# ProDoc_promicro_e22P_Tomas_2026-05-28.net
KiCad netlist of a schematic drawn in EasyEDA Pro
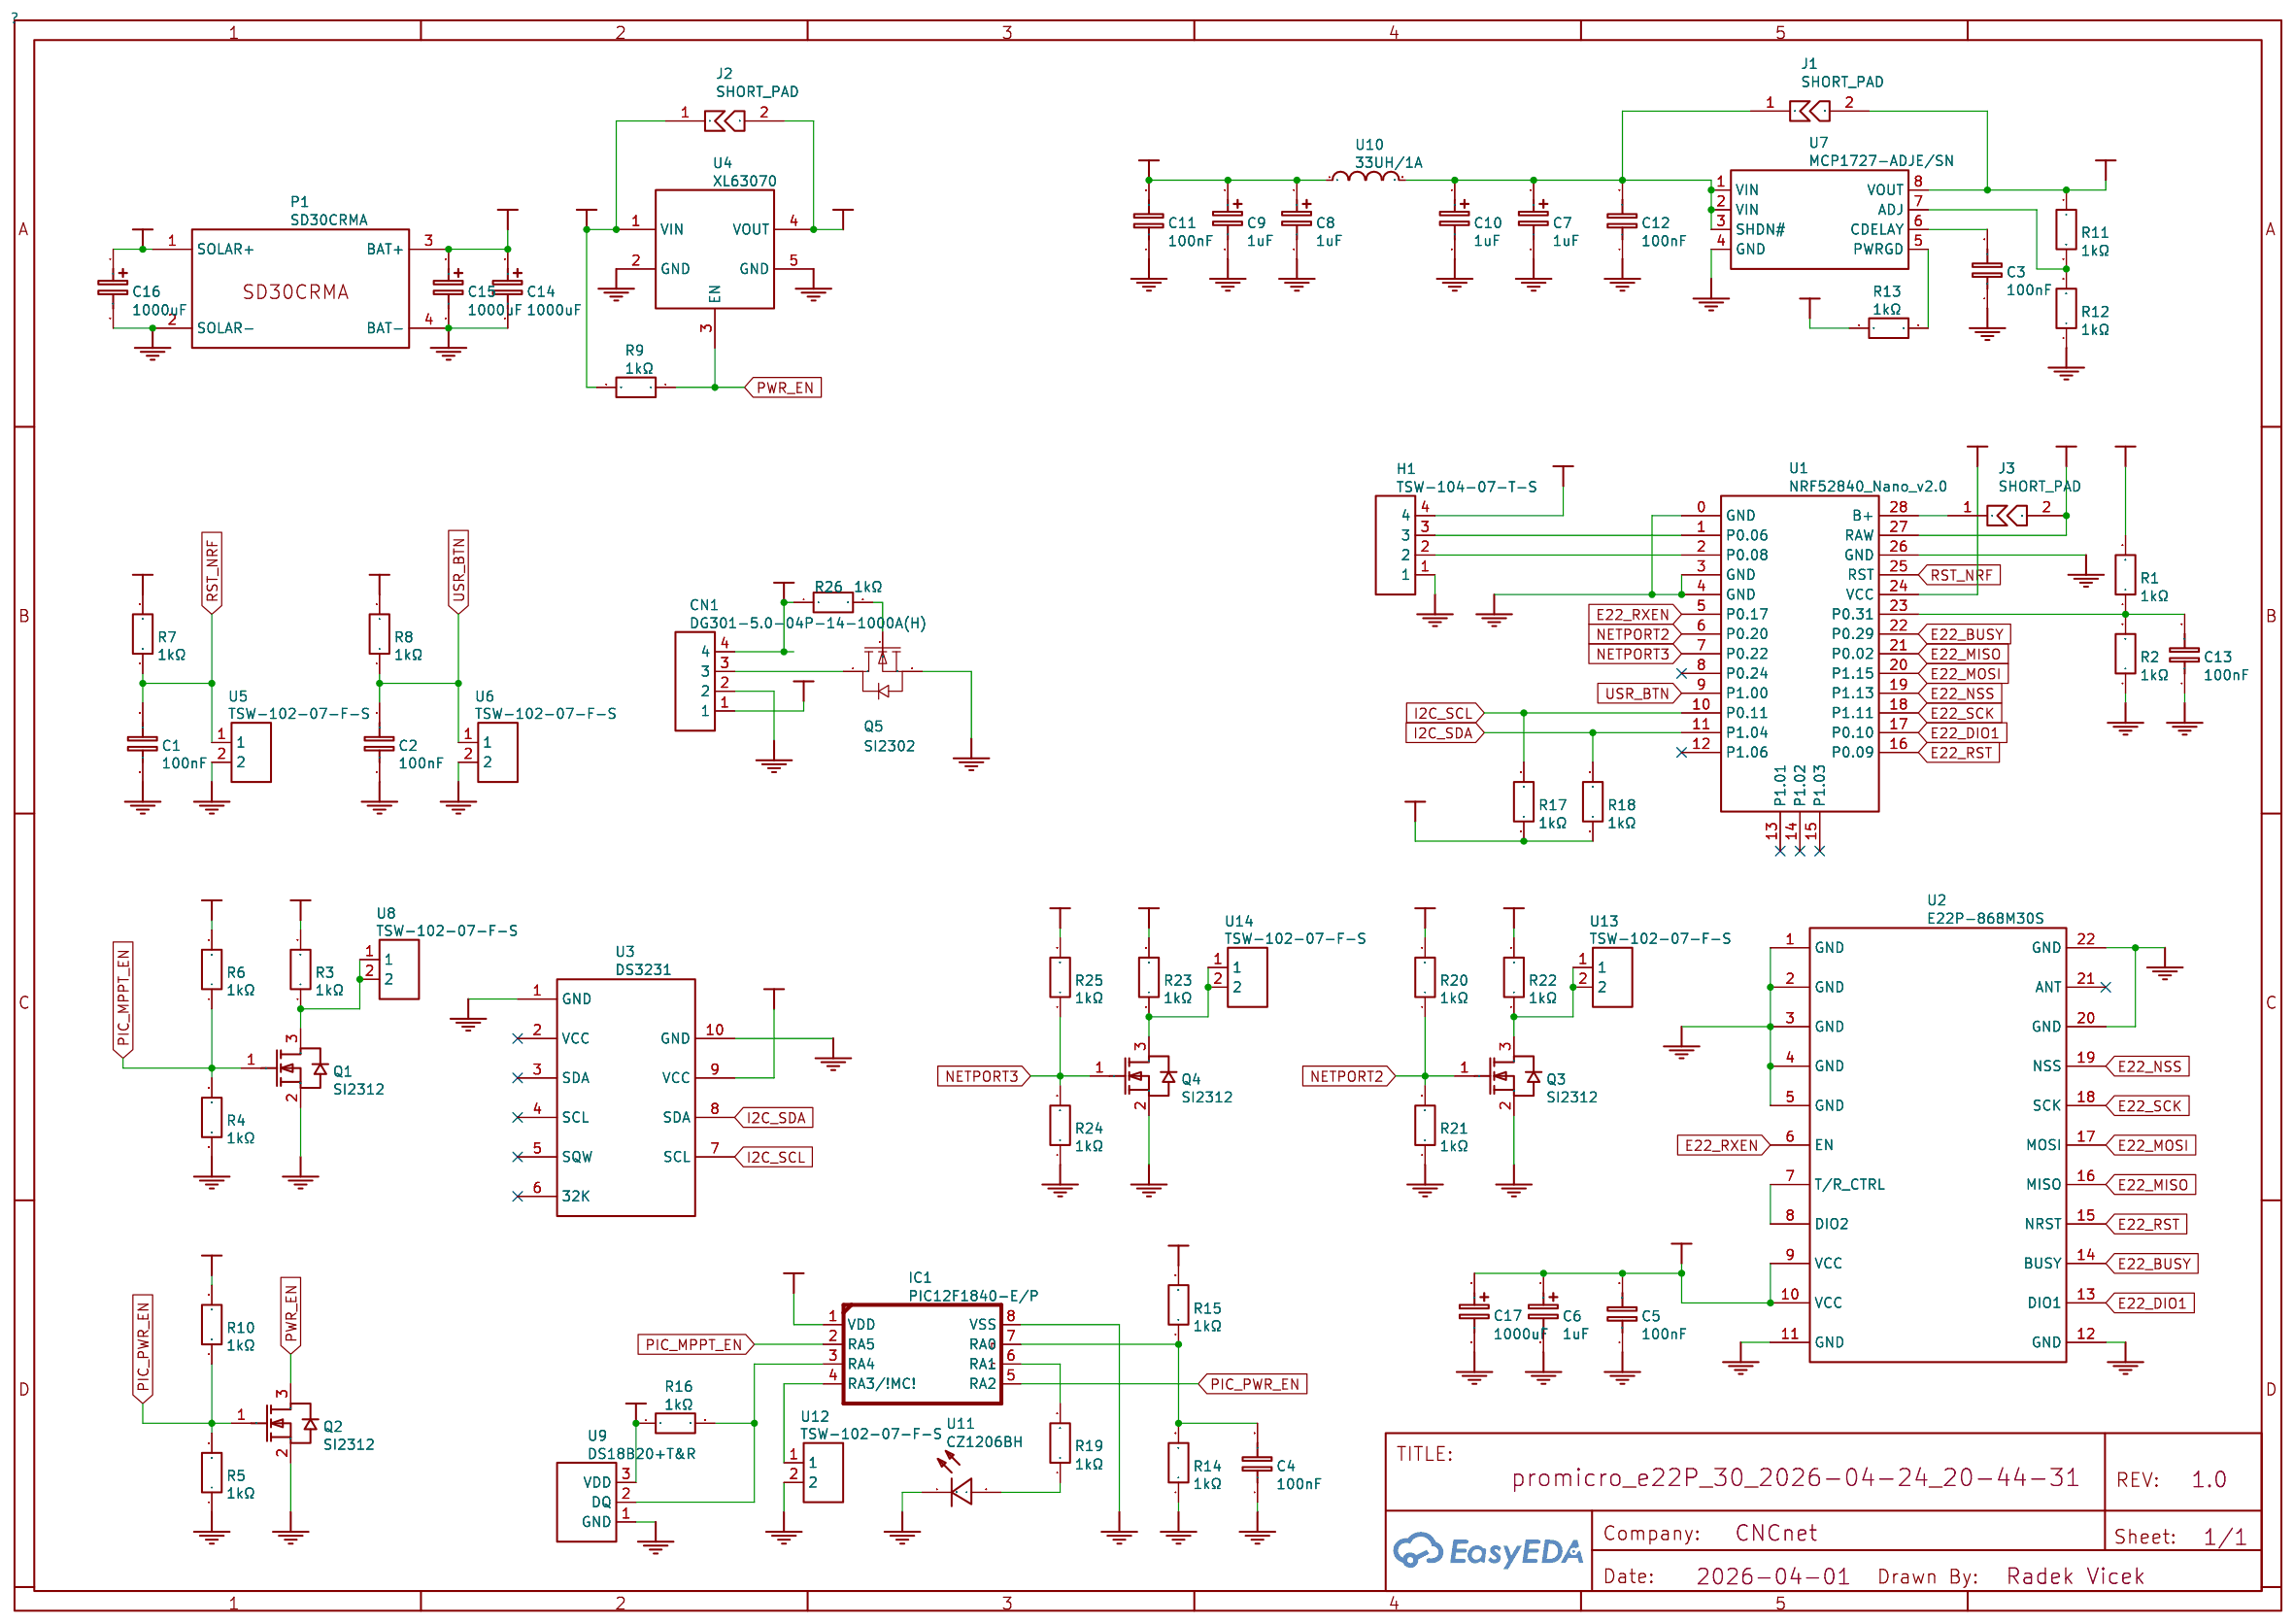
[diagram p0: schematic sheet]

(export (version "E")
  (design (tool "Eeschema 10.0.6"))
  (components
    (comp (ref "C1")
      (value "100nF")
      (description "Capacitance:100nF Tolerance:±10% Tolerance:±10% Voltage Rating:50V Temperature Coefficient:-")
      (fields
        (field (name "Manufacturer Part") "CT41G-0805-2X1-50V-0.1uF-K(N)")
        (field (name "Manufacturer") "TORCH(火炬)")
      )
      (libsource (lib "easyedapro") (part "0.1u"))
    )
    (comp (ref "C2")
      (value "100nF")
      (description "Capacitance:100nF Tolerance:±10% Tolerance:±10% Voltage Rating:50V Temperature Coefficient:-")
      (fields
        (field (name "Manufacturer Part") "CT41G-0805-2X1-50V-0.1uF-K(N)")
        (field (name "Manufacturer") "TORCH(火炬)")
      )
      (libsource (lib "easyedapro") (part "0.1u"))
    )
    (comp (ref "C3")
      (value "100nF")
      (description "Capacitance:100nF Tolerance:±10% Tolerance:±10% Voltage Rating:50V Temperature Coefficient:-")
      (fields
        (field (name "Manufacturer Part") "CT41G-0805-2X1-50V-0.1uF-K(N)")
        (field (name "Manufacturer") "TORCH(火炬)")
      )
      (libsource (lib "easyedapro") (part "0.1u"))
    )
    (comp (ref "C4")
      (value "100nF")
      (description "Capacitance:100nF Tolerance:±10% Tolerance:±10% Voltage Rating:50V Temperature Coefficient:-")
      (fields
        (field (name "Manufacturer Part") "CT41G-0805-2X1-50V-0.1uF-K(N)")
        (field (name "Manufacturer") "TORCH(火炬)")
      )
      (libsource (lib "easyedapro") (part "0.1u"))
    )
    (comp (ref "C5")
      (value "100nF")
      (description "Capacitance:100nF Tolerance:±10% Tolerance:±10% Voltage Rating:50V Temperature Coefficient:-")
      (fields
        (field (name "Manufacturer Part") "CT41G-0805-2X1-50V-0.1uF-K(N)")
        (field (name "Manufacturer") "TORCH(火炬)")
      )
      (libsource (lib "easyedapro") (part "0.1u"))
    )
    (comp (ref "C6")
      (value "1uF")
      (fields (field (name "Manufacturer Part") "TAJB105K035RNJ") (field (name "Manufacturer") "Kyocera AVX"))
      (libsource (lib "easyedapro") (part "1u"))
    )
    (comp (ref "C7")
      (value "1uF")
      (fields (field (name "Manufacturer Part") "TAJB105K035RNJ") (field (name "Manufacturer") "Kyocera AVX"))
      (libsource (lib "easyedapro") (part "1u"))
    )
    (comp (ref "C8")
      (value "1uF")
      (fields (field (name "Manufacturer Part") "TAJB105K035RNJ") (field (name "Manufacturer") "Kyocera AVX"))
      (libsource (lib "easyedapro") (part "1u"))
    )
    (comp (ref "C9")
      (value "1uF")
      (fields (field (name "Manufacturer Part") "TAJB105K035RNJ") (field (name "Manufacturer") "Kyocera AVX"))
      (libsource (lib "easyedapro") (part "1u"))
    )
    (comp (ref "C10")
      (value "1uF")
      (fields (field (name "Manufacturer Part") "TAJB105K035RNJ") (field (name "Manufacturer") "Kyocera AVX"))
      (libsource (lib "easyedapro") (part "1u"))
    )
    (comp (ref "C11")
      (value "100nF")
      (description "Capacitance:100nF Tolerance:±10% Tolerance:±10% Voltage Rating:50V Temperature Coefficient:-")
      (fields
        (field (name "Manufacturer Part") "CT41G-0805-2X1-50V-0.1uF-K(N)")
        (field (name "Manufacturer") "TORCH(火炬)")
      )
      (libsource (lib "easyedapro") (part "0.1u"))
    )
    (comp (ref "C12")
      (value "100nF")
      (description "Capacitance:100nF Tolerance:±10% Tolerance:±10% Voltage Rating:50V Temperature Coefficient:-")
      (fields
        (field (name "Manufacturer Part") "CT41G-0805-2X1-50V-0.1uF-K(N)")
        (field (name "Manufacturer") "TORCH(火炬)")
      )
      (libsource (lib "easyedapro") (part "0.1u"))
    )
    (comp (ref "C13")
      (value "100nF")
      (description "Capacitance:100nF Tolerance:±10% Tolerance:±10% Voltage Rating:50V Temperature Coefficient:-")
      (fields
        (field (name "Manufacturer Part") "CT41G-0805-2X1-50V-0.1uF-K(N)")
        (field (name "Manufacturer") "TORCH(火炬)")
      )
      (libsource (lib "easyedapro") (part "0.1u"))
    )
    (comp (ref "C14")
      (value "1000uF")
      (fields (field (name "Manufacturer Part") "PB25V1000M8X17") (field (name "Manufacturer") "JIERR(捷而瑞)"))
      (libsource (lib "easyedapro") (part "1u"))
    )
    (comp (ref "C15")
      (value "1000uF")
      (fields (field (name "Manufacturer Part") "PB25V1000M8X17") (field (name "Manufacturer") "JIERR(捷而瑞)"))
      (libsource (lib "easyedapro") (part "1u"))
    )
    (comp (ref "C16")
      (value "1000uF")
      (fields (field (name "Manufacturer Part") "PB25V1000M8X17") (field (name "Manufacturer") "JIERR(捷而瑞)"))
      (libsource (lib "easyedapro") (part "1u"))
    )
    (comp (ref "C17")
      (value "1000uF")
      (fields (field (name "Manufacturer Part") "PB25V1000M8X17") (field (name "Manufacturer") "JIERR(捷而瑞)"))
      (libsource (lib "easyedapro") (part "1u"))
    )
    (comp (ref "CN1")
      (value "DG301-5.0-04P-14-1000A(H)")
      (footprint "easyedapro:CONN-TH_DEGSON_DG301-5.0-04P")
      (fields (field (name "Manufacturer") "DEGSON(高正/高松)") (field (name "Contributor") "lcsc"))
      (libsource (lib "easyedapro") (part "DG301-5.0-04P-14-1000A(H)"))
    )
    (comp (ref "H1")
      (value "TSW-104-07-T-S")
      (footprint "easyedapro:HDR-TH_4P-P2.54-V-M")
      (fields (field (name "Manufacturer") "SAMTEC") (field (name "Contributor") "lcsc"))
      (libsource (lib "easyedapro") (part "TSW-104-07-T-S"))
    )
    (comp (ref "IC1")
      (value "PIC12F1840-E/P")
      (fields (field (name "Manufacturer") "MICROCHIP(美国微芯)"))
      (libsource (lib "easyedapro") (part "PIC12F1840/P"))
    )
    (comp (ref "J1") (value "SHORT_PAD") (libsource (lib "easyedapro") (part "ShortPad")))
    (comp (ref "J2") (value "SHORT_PAD") (libsource (lib "easyedapro") (part "ShortPad")))
    (comp (ref "J3") (value "SHORT_PAD") (libsource (lib "easyedapro") (part "ShortPad")))
    (comp (ref "P1")
      (value "SD30CRMA")
      (footprint "easyedapro:SD30CRMA")
      (fields (field (name "Contributor") "mrilic66"))
      (libsource (lib "easyedapro") (part "SD30CRMA"))
    )
    (comp (ref "Q1")
      (value "SI2312")
      (footprint "easyedapro:SOT-23-3_L2.9-W1.3-P1.90-LS2.4-BR")
      (fields (field (name "Manufacturer") "PUOLOP(迪浦)") (field (name "Contributor") "LCSC"))
      (libsource (lib "easyedapro") (part "SI2312"))
    )
    (comp (ref "Q2")
      (value "SI2312")
      (footprint "easyedapro:SOT-23-3_L2.9-W1.3-P1.90-LS2.4-BR")
      (fields (field (name "Manufacturer") "PUOLOP(迪浦)") (field (name "Contributor") "LCSC"))
      (libsource (lib "easyedapro") (part "SI2312"))
    )
    (comp (ref "Q3")
      (value "SI2312")
      (footprint "easyedapro:SOT-23-3_L2.9-W1.3-P1.90-LS2.4-BR")
      (fields (field (name "Manufacturer") "PUOLOP(迪浦)") (field (name "Contributor") "LCSC"))
      (libsource (lib "easyedapro") (part "SI2312"))
    )
    (comp (ref "Q4")
      (value "SI2312")
      (footprint "easyedapro:SOT-23-3_L2.9-W1.3-P1.90-LS2.4-BR")
      (fields (field (name "Manufacturer") "PUOLOP(迪浦)") (field (name "Contributor") "LCSC"))
      (libsource (lib "easyedapro") (part "SI2312"))
    )
    (comp (ref "Q5")
      (value "SI2302")
      (footprint "easyedapro:SOT-23-3_L2.9-W1.3-P1.90-LS2.4-BR")
      (fields (field (name "Manufacturer") "FOSAN(富捷/富信)"))
      (libsource (lib "easyedapro") (part "SI2302_C20628873"))
    )
    (comp (ref "R1")
      (value "1kΩ")
      (fields (field (name "Manufacturer Part") "FRC0805J102 TS") (field (name "Manufacturer") "FOJAN(富捷)"))
      (libsource (lib "") (part "1k_1"))
    )
    (comp (ref "R2")
      (value "1kΩ")
      (fields (field (name "Manufacturer Part") "FRC0805J102 TS") (field (name "Manufacturer") "FOJAN(富捷)"))
      (libsource (lib "") (part "1k_1"))
    )
    (comp (ref "R3")
      (value "1kΩ")
      (fields (field (name "Manufacturer Part") "FRC0805J102 TS") (field (name "Manufacturer") "FOJAN(富捷)"))
      (libsource (lib "") (part "1k_1"))
    )
    (comp (ref "R4")
      (value "1kΩ")
      (fields (field (name "Manufacturer Part") "FRC0805J102 TS") (field (name "Manufacturer") "FOJAN(富捷)"))
      (libsource (lib "") (part "1k_1"))
    )
    (comp (ref "R5")
      (value "1kΩ")
      (fields (field (name "Manufacturer Part") "FRC0805J102 TS") (field (name "Manufacturer") "FOJAN(富捷)"))
      (libsource (lib "") (part "1k_1"))
    )
    (comp (ref "R6")
      (value "1kΩ")
      (fields (field (name "Manufacturer Part") "FRC0805J102 TS") (field (name "Manufacturer") "FOJAN(富捷)"))
      (libsource (lib "") (part "1k_1"))
    )
    (comp (ref "R7")
      (value "1kΩ")
      (fields (field (name "Manufacturer Part") "FRC0805J102 TS") (field (name "Manufacturer") "FOJAN(富捷)"))
      (libsource (lib "") (part "1k_1"))
    )
    (comp (ref "R8")
      (value "1kΩ")
      (fields (field (name "Manufacturer Part") "FRC0805J102 TS") (field (name "Manufacturer") "FOJAN(富捷)"))
      (libsource (lib "") (part "1k_1"))
    )
    (comp (ref "R9")
      (value "1kΩ")
      (fields (field (name "Manufacturer Part") "FRC0805J102 TS") (field (name "Manufacturer") "FOJAN(富捷)"))
      (libsource (lib "easyedapro") (part "1k"))
    )
    (comp (ref "R10")
      (value "1kΩ")
      (fields (field (name "Manufacturer Part") "FRC0805J102 TS") (field (name "Manufacturer") "FOJAN(富捷)"))
      (libsource (lib "") (part "1k_1"))
    )
    (comp (ref "R11")
      (value "1kΩ")
      (fields (field (name "Manufacturer Part") "FRC0805J102 TS") (field (name "Manufacturer") "FOJAN(富捷)"))
      (libsource (lib "") (part "1k_2"))
    )
    (comp (ref "R12")
      (value "1kΩ")
      (fields (field (name "Manufacturer Part") "FRC0805J102 TS") (field (name "Manufacturer") "FOJAN(富捷)"))
      (libsource (lib "") (part "1k_1"))
    )
    (comp (ref "R13")
      (value "1kΩ")
      (fields (field (name "Manufacturer Part") "FRC0805J102 TS") (field (name "Manufacturer") "FOJAN(富捷)"))
      (libsource (lib "easyedapro") (part "1k"))
    )
    (comp (ref "R14")
      (value "1kΩ")
      (fields (field (name "Manufacturer Part") "FRC0805J102 TS") (field (name "Manufacturer") "FOJAN(富捷)"))
      (libsource (lib "") (part "1k_1"))
    )
    (comp (ref "R15")
      (value "1kΩ")
      (fields (field (name "Manufacturer Part") "FRC0805J102 TS") (field (name "Manufacturer") "FOJAN(富捷)"))
      (libsource (lib "") (part "1k_1"))
    )
    (comp (ref "R16")
      (value "1kΩ")
      (fields (field (name "Manufacturer Part") "FRC0805J102 TS") (field (name "Manufacturer") "FOJAN(富捷)"))
      (libsource (lib "") (part "1k_3"))
    )
    (comp (ref "R17")
      (value "1kΩ")
      (fields (field (name "Manufacturer Part") "FRC0805J102 TS") (field (name "Manufacturer") "FOJAN(富捷)"))
      (libsource (lib "") (part "1k_1"))
    )
    (comp (ref "R18")
      (value "1kΩ")
      (fields (field (name "Manufacturer Part") "FRC0805J102 TS") (field (name "Manufacturer") "FOJAN(富捷)"))
      (libsource (lib "") (part "1k_1"))
    )
    (comp (ref "R19")
      (value "1kΩ")
      (fields (field (name "Manufacturer Part") "FRC0805J102 TS") (field (name "Manufacturer") "FOJAN(富捷)"))
      (libsource (lib "") (part "1k_1"))
    )
    (comp (ref "R20")
      (value "1kΩ")
      (fields (field (name "Manufacturer Part") "FRC0805J102 TS") (field (name "Manufacturer") "FOJAN(富捷)"))
      (libsource (lib "") (part "1k_1"))
    )
    (comp (ref "R21")
      (value "1kΩ")
      (fields (field (name "Manufacturer Part") "FRC0805J102 TS") (field (name "Manufacturer") "FOJAN(富捷)"))
      (libsource (lib "") (part "1k_1"))
    )
    (comp (ref "R22")
      (value "1kΩ")
      (fields (field (name "Manufacturer Part") "FRC0805J102 TS") (field (name "Manufacturer") "FOJAN(富捷)"))
      (libsource (lib "") (part "1k_1"))
    )
    (comp (ref "R23")
      (value "1kΩ")
      (fields (field (name "Manufacturer Part") "FRC0805J102 TS") (field (name "Manufacturer") "FOJAN(富捷)"))
      (libsource (lib "") (part "1k_1"))
    )
    (comp (ref "R24")
      (value "1kΩ")
      (fields (field (name "Manufacturer Part") "FRC0805J102 TS") (field (name "Manufacturer") "FOJAN(富捷)"))
      (libsource (lib "") (part "1k_1"))
    )
    (comp (ref "R25")
      (value "1kΩ")
      (fields (field (name "Manufacturer Part") "FRC0805J102 TS") (field (name "Manufacturer") "FOJAN(富捷)"))
      (libsource (lib "") (part "1k_1"))
    )
    (comp (ref "R26")
      (value "1kΩ")
      (fields (field (name "Manufacturer Part") "FRC0805J102 TS") (field (name "Manufacturer") "FOJAN(富捷)"))
      (libsource (lib "easyedapro") (part "1k"))
    )
    (comp (ref "U1")
      (value "NRF52840_Nano_v2.0")
      (footprint "easyedapro:NRF52840_NANO_V2,0")
      (fields (field (name "Contributor") "eugeniomercol"))
      (libsource (lib "easyedapro") (part "NRF52840_Nano_v2.0"))
    )
    (comp (ref "U2")
      (value "E22P-868M30S")
      (fields (field (name "Manufacturer") "EBYTE(亿佰特)"))
      (libsource (lib "easyedapro") (part "E22P-868M30S"))
    )
    (comp (ref "U3")
      (value "DS3231")
      (footprint "easyedapro:DS3231")
      (fields (field (name "Manufacturer") "IIOTSME") (field (name "Contributor") "mazran.iiotsme"))
      (libsource (lib "easyedapro") (part "DS3231"))
    )
    (comp (ref "U4")
      (value "XL63070")
      (footprint "easyedapro:XL63070")
      (fields (field (name "Contributor") "willyjestrabek"))
      (libsource (lib "easyedapro") (part "XL63070"))
    )
    (comp (ref "U5")
      (value "TSW-102-07-F-S")
      (footprint "easyedapro:HDR-TH_2P-P2.54-V-M-3")
      (fields (field (name "Manufacturer") "SAMTEC") (field (name "Contributor") "lcsc"))
      (libsource (lib "easyedapro") (part "TSW-102-07-F-S"))
    )
    (comp (ref "U6")
      (value "TSW-102-07-F-S")
      (footprint "easyedapro:HDR-TH_2P-P2.54-V-M-3")
      (fields (field (name "Manufacturer") "SAMTEC") (field (name "Contributor") "lcsc"))
      (libsource (lib "easyedapro") (part "TSW-102-07-F-S"))
    )
    (comp (ref "U7")
      (value "MCP1727-ADJE/SN")
      (footprint "easyedapro:SOIC-8_L4.9-W3.9-P1.27-LS6.0-BL")
      (fields (field (name "Manufacturer") "MICROCHIP(美国微芯)") (field (name "Contributor") "LCSC"))
      (libsource (lib "easyedapro") (part "MCP1727-ADJE/SN"))
    )
    (comp (ref "U8")
      (value "TSW-102-07-F-S")
      (footprint "easyedapro:HDR-TH_2P-P2.54-V-M-3")
      (fields (field (name "Manufacturer") "SAMTEC") (field (name "Contributor") "lcsc"))
      (libsource (lib "easyedapro") (part "TSW-102-07-F-S"))
    )
    (comp (ref "U9")
      (value "DS18B20+T&R")
      (footprint "easyedapro:TO-92-3_L4.9-W3.7-P2.54-L")
      (fields (field (name "Manufacturer") "ADI(亚德诺)/MAXIM(美信)") (field (name "Contributor") "LCSC"))
      (libsource (lib "easyedapro") (part "DS18B20+T&amp;R"))
    )
    (comp (ref "U10")
      (value "33UH/1A")
      (footprint "easyedapro:IND-TH_BD10.0-P5.00-D0.6")
      (fields (field (name "Manufacturer Part") "33uH/1A") (field (name "Contributor") "lcsc"))
      (libsource (lib "easyedapro") (part "33UH/1A"))
    )
    (comp (ref "U11")
      (value "CZ1206BH")
      (footprint "easyedapro:LED-SMD_CZ1206BH")
      (fields (field (name "Contributor") "lcsc"))
      (libsource (lib "easyedapro") (part "CZ1206BH"))
    )
    (comp (ref "U12")
      (value "TSW-102-07-F-S")
      (footprint "easyedapro:HDR-TH_2P-P2.54-V-M-3")
      (fields (field (name "Manufacturer") "SAMTEC") (field (name "Contributor") "lcsc"))
      (libsource (lib "easyedapro") (part "TSW-102-07-F-S"))
    )
    (comp (ref "U13")
      (value "TSW-102-07-F-S")
      (footprint "easyedapro:HDR-TH_2P-P2.54-V-M-3")
      (fields (field (name "Manufacturer") "SAMTEC") (field (name "Contributor") "lcsc"))
      (libsource (lib "easyedapro") (part "TSW-102-07-F-S"))
    )
    (comp (ref "U14")
      (value "TSW-102-07-F-S")
      (footprint "easyedapro:HDR-TH_2P-P2.54-V-M-3")
      (fields (field (name "Manufacturer") "SAMTEC") (field (name "Contributor") "lcsc"))
      (libsource (lib "easyedapro") (part "TSW-102-07-F-S"))
    )
  )
  (nets
    (net (code "1") (name "+3V3") (class "Default")
      (node (ref "H1") (pin "4") (pinfunction "4_4") (pintype "unspecified"))
      (node (ref "R10") (pin "2") (pinfunction "2_2") (pintype "unspecified"))
      (node (ref "R17") (pin "1") (pinfunction "1_1") (pintype "unspecified"))
      (node (ref "R18") (pin "1") (pinfunction "1_1") (pintype "unspecified"))
      (node (ref "R20") (pin "2") (pinfunction "2_2") (pintype "unspecified"))
      (node (ref "R22") (pin "2") (pinfunction "2_2") (pintype "unspecified"))
      (node (ref "R23") (pin "2") (pinfunction "2_2") (pintype "unspecified"))
      (node (ref "R25") (pin "2") (pinfunction "2_2") (pintype "unspecified"))
      (node (ref "R3") (pin "2") (pinfunction "2_2") (pintype "unspecified"))
      (node (ref "R6") (pin "2") (pinfunction "2_2") (pintype "unspecified"))
      (node (ref "R7") (pin "2") (pinfunction "2_2") (pintype "unspecified"))
      (node (ref "R8") (pin "2") (pinfunction "2_2") (pintype "unspecified"))
      (node (ref "U1") (pin "24") (pinfunction "VCC_24") (pintype "bidirectional"))
      (node (ref "U3") (pin "9") (pinfunction "VCC_9") (pintype "unspecified"))
    )
    (net (code "2") (name "+5V") (class "Default")
      (node (ref "C11") (pin "2") (pinfunction "2_2") (pintype "unspecified"))
      (node (ref "C8") (pin "1") (pinfunction "1_1") (pintype "unspecified"))
      (node (ref "C9") (pin "1") (pinfunction "1_1") (pintype "unspecified"))
      (node (ref "J2") (pin "2") (pinfunction "2_2") (pintype "unspecified"))
      (node (ref "U10") (pin "1") (pinfunction "1_1") (pintype "unspecified"))
      (node (ref "U4") (pin "4") (pinfunction "VOUT_4") (pintype "unspecified"))
    )
    (net (code "3") (name "E22_BUSY") (class "Default")
      (node (ref "U1") (pin "22") (pinfunction "P0.29_22") (pintype "bidirectional"))
      (node (ref "U2") (pin "14") (pinfunction "BUSY_14") (pintype "unspecified"))
    )
    (net (code "4") (name "E22_DIO1") (class "Default")
      (node (ref "U1") (pin "17") (pinfunction "P0.10_17") (pintype "bidirectional"))
      (node (ref "U2") (pin "13") (pinfunction "DIO1_13") (pintype "unspecified"))
    )
    (net (code "5") (name "E22_MISO") (class "Default")
      (node (ref "U1") (pin "21") (pinfunction "P0.02_21") (pintype "bidirectional"))
      (node (ref "U2") (pin "16") (pinfunction "MISO_16") (pintype "unspecified"))
    )
    (net (code "6") (name "E22_MOSI") (class "Default")
      (node (ref "U1") (pin "20") (pinfunction "P1.15_20") (pintype "bidirectional"))
      (node (ref "U2") (pin "17") (pinfunction "MOSI_17") (pintype "unspecified"))
    )
    (net (code "7") (name "E22_NSS") (class "Default")
      (node (ref "U1") (pin "19") (pinfunction "P1.13_19") (pintype "bidirectional"))
      (node (ref "U2") (pin "19") (pinfunction "NSS_19") (pintype "unspecified"))
    )
    (net (code "8") (name "E22_RST") (class "Default")
      (node (ref "U1") (pin "16") (pinfunction "P0.09_16") (pintype "bidirectional"))
      (node (ref "U2") (pin "15") (pinfunction "NRST_15") (pintype "unspecified"))
    )
    (net (code "9") (name "E22_RXEN") (class "Default")
      (node (ref "U1") (pin "5") (pinfunction "P0.17_5") (pintype "unspecified"))
      (node (ref "U2") (pin "6") (pinfunction "EN_6") (pintype "unspecified"))
    )
    (net (code "10") (name "E22_SCK") (class "Default")
      (node (ref "U1") (pin "18") (pinfunction "P1.11_18") (pintype "bidirectional"))
      (node (ref "U2") (pin "18") (pinfunction "SCK_18") (pintype "unspecified"))
    )
    (net (code "11") (name "GND") (class "Default")
      (node (ref "C1") (pin "1") (pinfunction "1_1") (pintype "unspecified"))
      (node (ref "C10") (pin "2") (pinfunction "2_2") (pintype "unspecified"))
      (node (ref "C11") (pin "1") (pinfunction "1_1") (pintype "unspecified"))
      (node (ref "C12") (pin "1") (pinfunction "1_1") (pintype "unspecified"))
      (node (ref "C13") (pin "1") (pinfunction "1_1") (pintype "unspecified"))
      (node (ref "C14") (pin "2") (pinfunction "2_2") (pintype "unspecified"))
      (node (ref "C15") (pin "2") (pinfunction "2_2") (pintype "unspecified"))
      (node (ref "C16") (pin "2") (pinfunction "2_2") (pintype "unspecified"))
      (node (ref "C17") (pin "2") (pinfunction "2_2") (pintype "unspecified"))
      (node (ref "C2") (pin "1") (pinfunction "1_1") (pintype "unspecified"))
      (node (ref "C3") (pin "1") (pinfunction "1_1") (pintype "unspecified"))
      (node (ref "C4") (pin "1") (pinfunction "1_1") (pintype "unspecified"))
      (node (ref "C5") (pin "1") (pinfunction "1_1") (pintype "unspecified"))
      (node (ref "C6") (pin "2") (pinfunction "2_2") (pintype "unspecified"))
      (node (ref "C7") (pin "2") (pinfunction "2_2") (pintype "unspecified"))
      (node (ref "C8") (pin "2") (pinfunction "2_2") (pintype "unspecified"))
      (node (ref "C9") (pin "2") (pinfunction "2_2") (pintype "unspecified"))
      (node (ref "CN1") (pin "2") (pinfunction "2_2") (pintype "unspecified"))
      (node (ref "H1") (pin "1") (pinfunction "1_1") (pintype "unspecified"))
      (node (ref "IC1") (pin "8") (pinfunction "VSS_8") (pintype "bidirectional"))
      (node (ref "P1") (pin "2") (pinfunction "SOLAR-_2") (pintype "unspecified"))
      (node (ref "P1") (pin "4") (pinfunction "BAT-_4") (pintype "unspecified"))
      (node (ref "Q1") (pin "2") (pinfunction "S_2") (pintype "unspecified"))
      (node (ref "Q2") (pin "2") (pinfunction "S_2") (pintype "unspecified"))
      (node (ref "Q3") (pin "2") (pinfunction "S_2") (pintype "unspecified"))
      (node (ref "Q4") (pin "2") (pinfunction "S_2") (pintype "unspecified"))
      (node (ref "Q5") (pin "2") (pinfunction "S_2") (pintype "unspecified"))
      (node (ref "R12") (pin "1") (pinfunction "1_1") (pintype "unspecified"))
      (node (ref "R14") (pin "1") (pinfunction "1_1") (pintype "unspecified"))
      (node (ref "R2") (pin "1") (pinfunction "1_1") (pintype "unspecified"))
      (node (ref "R21") (pin "1") (pinfunction "1_1") (pintype "unspecified"))
      (node (ref "R24") (pin "1") (pinfunction "1_1") (pintype "unspecified"))
      (node (ref "R4") (pin "1") (pinfunction "1_1") (pintype "unspecified"))
      (node (ref "R5") (pin "1") (pinfunction "1_1") (pintype "unspecified"))
      (node (ref "U1") (pin "0") (pinfunction "GND_0") (pintype "unspecified"))
      (node (ref "U1") (pin "26") (pinfunction "GND_26") (pintype "bidirectional"))
      (node (ref "U1") (pin "3") (pinfunction "GND_3") (pintype "unspecified"))
      (node (ref "U1") (pin "4") (pinfunction "GND_4") (pintype "unspecified"))
      (node (ref "U11") (pin "1") (pinfunction "C_1") (pintype "unspecified"))
      (node (ref "U12") (pin "2") (pinfunction "2_2") (pintype "unspecified"))
      (node (ref "U2") (pin "1") (pinfunction "GND_1") (pintype "unspecified"))
      (node (ref "U2") (pin "11") (pinfunction "GND_11") (pintype "unspecified"))
      (node (ref "U2") (pin "12") (pinfunction "GND_12") (pintype "unspecified"))
      (node (ref "U2") (pin "2") (pinfunction "GND_2") (pintype "unspecified"))
      (node (ref "U2") (pin "20") (pinfunction "GND_20") (pintype "unspecified"))
      (node (ref "U2") (pin "22") (pinfunction "GND_22") (pintype "unspecified"))
      (node (ref "U2") (pin "3") (pinfunction "GND_3") (pintype "unspecified"))
      (node (ref "U2") (pin "4") (pinfunction "GND_4") (pintype "unspecified"))
      (node (ref "U2") (pin "5") (pinfunction "GND_5") (pintype "unspecified"))
      (node (ref "U3") (pin "1") (pinfunction "GND_1") (pintype "unspecified"))
      (node (ref "U3") (pin "10") (pinfunction "GND_10") (pintype "unspecified"))
      (node (ref "U4") (pin "2") (pinfunction "GND_2") (pintype "unspecified"))
      (node (ref "U4") (pin "5") (pinfunction "GND_5") (pintype "unspecified"))
      (node (ref "U5") (pin "2") (pinfunction "2_2") (pintype "unspecified"))
      (node (ref "U6") (pin "2") (pinfunction "2_2") (pintype "unspecified"))
      (node (ref "U7") (pin "4") (pinfunction "GND_4") (pintype "unspecified"))
      (node (ref "U9") (pin "1") (pinfunction "GND_1") (pintype "unspecified"))
    )
    (net (code "12") (name "I2C_SCL") (class "Default")
      (node (ref "R17") (pin "2") (pinfunction "2_2") (pintype "unspecified"))
      (node (ref "U1") (pin "10") (pinfunction "P0.11_10") (pintype "unspecified"))
      (node (ref "U3") (pin "7") (pinfunction "SCL_7") (pintype "unspecified"))
    )
    (net (code "13") (name "I2C_SDA") (class "Default")
      (node (ref "R18") (pin "2") (pinfunction "2_2") (pintype "unspecified"))
      (node (ref "U1") (pin "11") (pinfunction "P1.04_11") (pintype "unspecified"))
      (node (ref "U3") (pin "8") (pinfunction "SDA_8") (pintype "unspecified"))
    )
    (net (code "14") (name "NETPORT2") (class "Default")
      (node (ref "Q3") (pin "1") (pinfunction "G_1") (pintype "unspecified"))
      (node (ref "R20") (pin "1") (pinfunction "1_1") (pintype "unspecified"))
      (node (ref "R21") (pin "2") (pinfunction "2_2") (pintype "unspecified"))
      (node (ref "U1") (pin "6") (pinfunction "P0.20_6") (pintype "unspecified"))
    )
    (net (code "15") (name "NETPORT3") (class "Default")
      (node (ref "Q4") (pin "1") (pinfunction "G_1") (pintype "unspecified"))
      (node (ref "R24") (pin "2") (pinfunction "2_2") (pintype "unspecified"))
      (node (ref "R25") (pin "1") (pinfunction "1_1") (pintype "unspecified"))
      (node (ref "U1") (pin "7") (pinfunction "P0.22_7") (pintype "unspecified"))
    )
    (net (code "16") (name "Net-(IC1-RA0)") (class "Default")
      (node (ref "C4") (pin "2") (pinfunction "2_2") (pintype "unspecified"))
      (node (ref "IC1") (pin "7") (pinfunction "RA0_7") (pintype "bidirectional"))
      (node (ref "R14") (pin "2") (pinfunction "2_2") (pintype "unspecified"))
      (node (ref "R15") (pin "1") (pinfunction "1_1") (pintype "unspecified"))
    )
    (net (code "17") (name "Net-(IC1-RA1)") (class "Default")
      (node (ref "IC1") (pin "6") (pinfunction "RA1_6") (pintype "bidirectional"))
      (node (ref "R19") (pin "2") (pinfunction "2_2") (pintype "unspecified"))
    )
    (net (code "18") (name "Net-(IC1-RA3{slash}!MC!)") (class "Default")
      (node (ref "IC1") (pin "4") (pinfunction "RA3/!MC!_4") (pintype "bidirectional"))
      (node (ref "U12") (pin "1") (pinfunction "1_1") (pintype "unspecified"))
    )
    (net (code "19") (name "Net-(IC1-RA4)") (class "Default")
      (node (ref "IC1") (pin "3") (pinfunction "RA4_3") (pintype "bidirectional"))
      (node (ref "R16") (pin "2") (pinfunction "2_2") (pintype "unspecified"))
      (node (ref "U9") (pin "2") (pinfunction "DQ_2") (pintype "unspecified"))
    )
    (net (code "20") (name "Net-(Q1-D)") (class "Default")
      (node (ref "Q1") (pin "3") (pinfunction "D_3") (pintype "unspecified"))
      (node (ref "R3") (pin "1") (pinfunction "1_1") (pintype "unspecified"))
      (node (ref "U8") (pin "1") (pinfunction "1_1") (pintype "unspecified"))
      (node (ref "U8") (pin "2") (pinfunction "2_2") (pintype "unspecified"))
    )
    (net (code "21") (name "Net-(Q3-D)") (class "Default")
      (node (ref "Q3") (pin "3") (pinfunction "D_3") (pintype "unspecified"))
      (node (ref "R22") (pin "1") (pinfunction "1_1") (pintype "unspecified"))
      (node (ref "U13") (pin "1") (pinfunction "1_1") (pintype "unspecified"))
      (node (ref "U13") (pin "2") (pinfunction "2_2") (pintype "unspecified"))
    )
    (net (code "22") (name "Net-(Q4-D)") (class "Default")
      (node (ref "Q4") (pin "3") (pinfunction "D_3") (pintype "unspecified"))
      (node (ref "R23") (pin "1") (pinfunction "1_1") (pintype "unspecified"))
      (node (ref "U14") (pin "1") (pinfunction "1_1") (pintype "unspecified"))
      (node (ref "U14") (pin "2") (pinfunction "2_2") (pintype "unspecified"))
    )
    (net (code "23") (name "Net-(Q5-D)") (class "Default")
      (node (ref "CN1") (pin "3") (pinfunction "3_3") (pintype "unspecified"))
      (node (ref "Q5") (pin "3") (pinfunction "D_3") (pintype "unspecified"))
    )
    (net (code "24") (name "Net-(Q5-G)") (class "Default")
      (node (ref "Q5") (pin "1") (pinfunction "G_1") (pintype "unspecified"))
      (node (ref "R26") (pin "2") (pinfunction "2_2") (pintype "unspecified"))
    )
    (net (code "25") (name "Net-(U1-B+)") (class "Default")
      (node (ref "J3") (pin "1") (pinfunction "1_1") (pintype "unspecified"))
      (node (ref "U1") (pin "28") (pinfunction "B+_28") (pintype "bidirectional"))
    )
    (net (code "26") (name "Net-(U1-P0.06)") (class "Default")
      (node (ref "H1") (pin "3") (pinfunction "3_3") (pintype "unspecified"))
      (node (ref "U1") (pin "1") (pinfunction "P0.06_1") (pintype "unspecified"))
    )
    (net (code "27") (name "Net-(U1-P0.08)") (class "Default")
      (node (ref "H1") (pin "2") (pinfunction "2_2") (pintype "unspecified"))
      (node (ref "U1") (pin "2") (pinfunction "P0.08_2") (pintype "input"))
    )
    (net (code "28") (name "Net-(U1-P0.31)") (class "Default")
      (node (ref "C13") (pin "2") (pinfunction "2_2") (pintype "unspecified"))
      (node (ref "R1") (pin "1") (pinfunction "1_1") (pintype "unspecified"))
      (node (ref "R2") (pin "2") (pinfunction "2_2") (pintype "unspecified"))
      (node (ref "U1") (pin "23") (pinfunction "P0.31_23") (pintype "bidirectional"))
    )
    (net (code "29") (name "Net-(U2-DIO2)") (class "Default")
      (node (ref "U2") (pin "7") (pinfunction "T/R_CTRL_7") (pintype "unspecified"))
      (node (ref "U2") (pin "8") (pinfunction "DIO2_8") (pintype "unspecified"))
    )
    (net (code "30") (name "Net-(U7-ADJ)") (class "Default")
      (node (ref "R11") (pin "2") (pinfunction "2_2") (pintype "unspecified"))
      (node (ref "R12") (pin "2") (pinfunction "2_2") (pintype "unspecified"))
      (node (ref "U7") (pin "7") (pinfunction "ADJ_7") (pintype "unspecified"))
    )
    (net (code "31") (name "Net-(U7-CDELAY)") (class "Default")
      (node (ref "C3") (pin "2") (pinfunction "2_2") (pintype "unspecified"))
      (node (ref "U7") (pin "6") (pinfunction "CDELAY_6") (pintype "unspecified"))
    )
    (net (code "32") (name "Net-(U7-PWRGD)") (class "Default")
      (node (ref "R13") (pin "1") (pinfunction "1_1") (pintype "unspecified"))
      (node (ref "U7") (pin "5") (pinfunction "PWRGD_5") (pintype "unspecified"))
    )
    (net (code "33") (name "Net-(U7-SHDN#)") (class "Default")
      (node (ref "C10") (pin "1") (pinfunction "1_1") (pintype "unspecified"))
      (node (ref "C12") (pin "2") (pinfunction "2_2") (pintype "unspecified"))
      (node (ref "C7") (pin "1") (pinfunction "1_1") (pintype "unspecified"))
      (node (ref "J1") (pin "1") (pinfunction "1_1") (pintype "unspecified"))
      (node (ref "U10") (pin "2") (pinfunction "2_2") (pintype "unspecified"))
      (node (ref "U7") (pin "1") (pinfunction "VIN_1") (pintype "unspecified"))
      (node (ref "U7") (pin "2") (pinfunction "VIN_2") (pintype "unspecified"))
      (node (ref "U7") (pin "3") (pinfunction "SHDN#_3") (pintype "unspecified"))
    )
    (net (code "34") (name "Net-(U11-A)") (class "Default")
      (node (ref "R19") (pin "1") (pinfunction "1_1") (pintype "unspecified"))
      (node (ref "U11") (pin "2") (pinfunction "A_2") (pintype "unspecified"))
    )
    (net (code "35") (name "PIC_MPPT_EN") (class "Default")
      (node (ref "IC1") (pin "2") (pinfunction "RA5_2") (pintype "bidirectional"))
      (node (ref "Q1") (pin "1") (pinfunction "G_1") (pintype "unspecified"))
      (node (ref "R4") (pin "2") (pinfunction "2_2") (pintype "unspecified"))
      (node (ref "R6") (pin "1") (pinfunction "1_1") (pintype "unspecified"))
    )
    (net (code "36") (name "PIC_PWR_EN") (class "Default")
      (node (ref "IC1") (pin "5") (pinfunction "RA2_5") (pintype "bidirectional"))
      (node (ref "Q2") (pin "1") (pinfunction "G_1") (pintype "unspecified"))
      (node (ref "R10") (pin "1") (pinfunction "1_1") (pintype "unspecified"))
      (node (ref "R5") (pin "2") (pinfunction "2_2") (pintype "unspecified"))
    )
    (net (code "37") (name "PWR_EN") (class "Default")
      (node (ref "Q2") (pin "3") (pinfunction "D_3") (pintype "unspecified"))
      (node (ref "R9") (pin "1") (pinfunction "1_1") (pintype "unspecified"))
      (node (ref "U4") (pin "3") (pinfunction "EN_3") (pintype "unspecified"))
    )
    (net (code "38") (name "RST_NRF") (class "Default")
      (node (ref "C1") (pin "2") (pinfunction "2_2") (pintype "unspecified"))
      (node (ref "R7") (pin "1") (pinfunction "1_1") (pintype "unspecified"))
      (node (ref "U1") (pin "25") (pinfunction "RST_25") (pintype "bidirectional"))
      (node (ref "U5") (pin "1") (pinfunction "1_1") (pintype "unspecified"))
    )
    (net (code "39") (name "USR_BTN") (class "Default")
      (node (ref "C2") (pin "2") (pinfunction "2_2") (pintype "unspecified"))
      (node (ref "R8") (pin "1") (pinfunction "1_1") (pintype "unspecified"))
      (node (ref "U1") (pin "9") (pinfunction "P1.00_9") (pintype "unspecified"))
      (node (ref "U6") (pin "1") (pinfunction "1_1") (pintype "unspecified"))
    )
    (net (code "40") (name "VBAT") (class "Default")
      (node (ref "C14") (pin "1") (pinfunction "1_1") (pintype "unspecified"))
      (node (ref "C15") (pin "1") (pinfunction "1_1") (pintype "unspecified"))
      (node (ref "CN1") (pin "4") (pinfunction "4_4") (pintype "unspecified"))
      (node (ref "IC1") (pin "1") (pinfunction "VDD_1") (pintype "bidirectional"))
      (node (ref "J2") (pin "1") (pinfunction "1_1") (pintype "unspecified"))
      (node (ref "P1") (pin "3") (pinfunction "BAT+_3") (pintype "unspecified"))
      (node (ref "R1") (pin "2") (pinfunction "2_2") (pintype "unspecified"))
      (node (ref "R15") (pin "2") (pinfunction "2_2") (pintype "unspecified"))
      (node (ref "R16") (pin "1") (pinfunction "1_1") (pintype "unspecified"))
      (node (ref "R26") (pin "1") (pinfunction "1_1") (pintype "unspecified"))
      (node (ref "R9") (pin "2") (pinfunction "2_2") (pintype "unspecified"))
      (node (ref "U4") (pin "1") (pinfunction "VIN_1") (pintype "unspecified"))
      (node (ref "U9") (pin "3") (pinfunction "VDD_3") (pintype "unspecified"))
    )
    (net (code "41") (name "VRAW") (class "Default")
      (node (ref "C17") (pin "1") (pinfunction "1_1") (pintype "unspecified"))
      (node (ref "C5") (pin "2") (pinfunction "2_2") (pintype "unspecified"))
      (node (ref "C6") (pin "1") (pinfunction "1_1") (pintype "unspecified"))
      (node (ref "J1") (pin "2") (pinfunction "2_2") (pintype "unspecified"))
      (node (ref "J3") (pin "2") (pinfunction "2_2") (pintype "unspecified"))
      (node (ref "R11") (pin "1") (pinfunction "1_1") (pintype "unspecified"))
      (node (ref "R13") (pin "2") (pinfunction "2_2") (pintype "unspecified"))
      (node (ref "U1") (pin "27") (pinfunction "RAW_27") (pintype "bidirectional"))
      (node (ref "U2") (pin "10") (pinfunction "VCC_10") (pintype "unspecified"))
      (node (ref "U2") (pin "9") (pinfunction "VCC_9") (pintype "unspecified"))
      (node (ref "U7") (pin "8") (pinfunction "VOUT_8") (pintype "unspecified"))
    )
    (net (code "42") (name "VSOL") (class "Default")
      (node (ref "C16") (pin "1") (pinfunction "1_1") (pintype "unspecified"))
      (node (ref "CN1") (pin "1") (pinfunction "1_1") (pintype "unspecified"))
      (node (ref "P1") (pin "1") (pinfunction "SOLAR+_1") (pintype "unspecified"))
    )
    (net (code "43") (name "unconnected-(U1-P0.24-Pad8)") (class "Default")
      (node (ref "U1") (pin "8") (pinfunction "P0.24_8") (pintype "unspecified+no_connect"))
    )
    (net (code "44") (name "unconnected-(U1-P1.01-Pad13)") (class "Default")
      (node (ref "U1") (pin "13") (pinfunction "P1.01_13") (pintype "unspecified+no_connect"))
    )
    (net (code "45") (name "unconnected-(U1-P1.02-Pad14)") (class "Default")
      (node (ref "U1") (pin "14") (pinfunction "P1.02_14") (pintype "unspecified+no_connect"))
    )
    (net (code "46") (name "unconnected-(U1-P1.03-Pad15)") (class "Default")
      (node (ref "U1") (pin "15") (pinfunction "P1.03_15") (pintype "unspecified+no_connect"))
    )
    (net (code "47") (name "unconnected-(U1-P1.06-Pad12)") (class "Default")
      (node (ref "U1") (pin "12") (pinfunction "P1.06_12") (pintype "unspecified+no_connect"))
    )
    (net (code "48") (name "unconnected-(U2-ANT-Pad21)") (class "Default")
      (node (ref "U2") (pin "21") (pinfunction "ANT_21") (pintype "unspecified+no_connect"))
    )
    (net (code "49") (name "unconnected-(U3-32K-Pad6)") (class "Default")
      (node (ref "U3") (pin "6") (pinfunction "32K_6") (pintype "unspecified+no_connect"))
    )
    (net (code "50") (name "unconnected-(U3-SCL-Pad4)") (class "Default")
      (node (ref "U3") (pin "4") (pinfunction "SCL_4") (pintype "unspecified+no_connect"))
    )
    (net (code "51") (name "unconnected-(U3-SDA-Pad3)") (class "Default")
      (node (ref "U3") (pin "3") (pinfunction "SDA_3") (pintype "unspecified+no_connect"))
    )
    (net (code "52") (name "unconnected-(U3-SQW-Pad5)") (class "Default")
      (node (ref "U3") (pin "5") (pinfunction "SQW_5") (pintype "unspecified+no_connect"))
    )
    (net (code "53") (name "unconnected-(U3-VCC-Pad2)") (class "Default")
      (node (ref "U3") (pin "2") (pinfunction "VCC_2") (pintype "unspecified+no_connect"))
    )
  )
)
